# GimbalMotorController2017.net
KiCad netlist of a schematic drawn in EAGLE
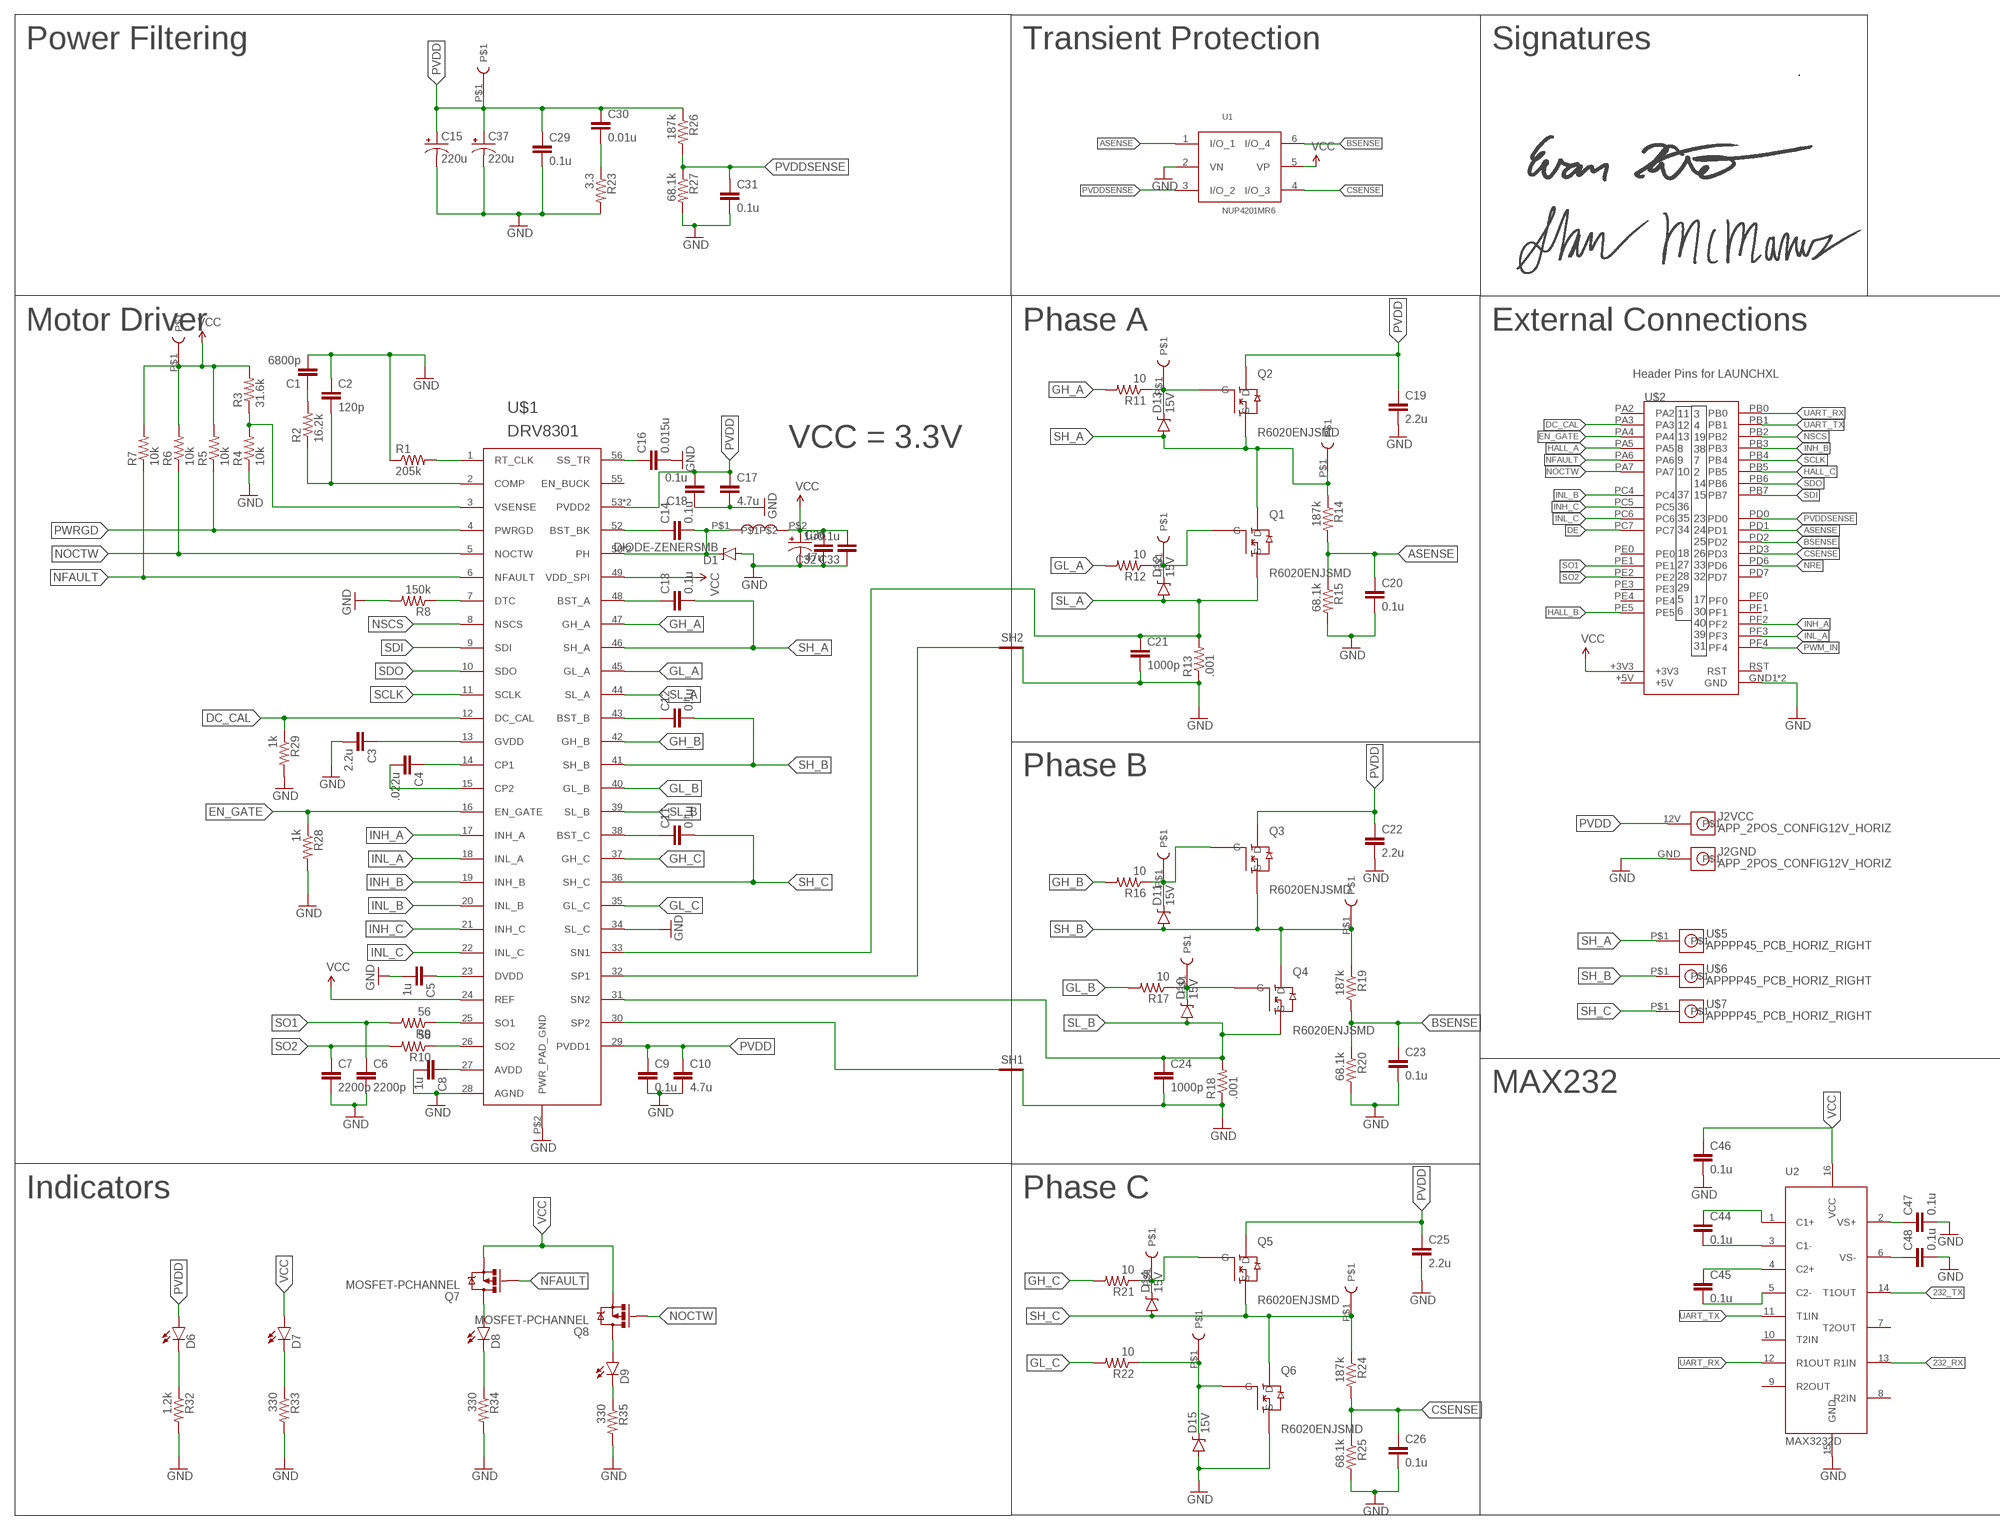
[diagram p0: schematic, sheet 1, part 1 of 2]
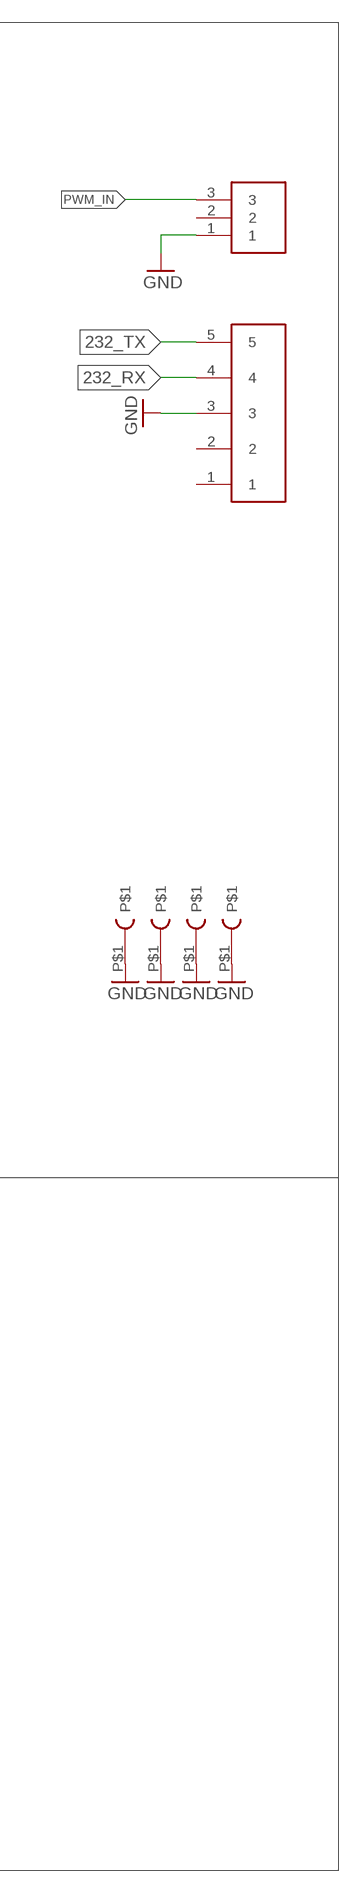
[diagram p1: schematic, sheet 1, part 2 of 2]

(export (version "E")
  (design (tool "Eeschema 10.0.6"))
  (components
    (comp (ref "C1")
      (value "6800p")
      (footprint "eagle-import:0805")
      (libsource (lib "eagle-import") (part "CAP0805"))
    )
    (comp (ref "C2")
      (value "120p")
      (footprint "eagle-import:0805")
      (libsource (lib "eagle-import") (part "CAP0805"))
    )
    (comp (ref "C3")
      (value "2.2u")
      (footprint "eagle-import:1206")
      (libsource (lib "eagle-import") (part "CAP1206"))
    )
    (comp (ref "C4")
      (value ".022u")
      (footprint "eagle-import:0805")
      (libsource (lib "eagle-import") (part "CAP0805"))
    )
    (comp (ref "C5")
      (value "1u")
      (footprint "eagle-import:0805")
      (libsource (lib "eagle-import") (part "CAP0805"))
    )
    (comp (ref "C6")
      (value "2200p")
      (footprint "eagle-import:0805")
      (libsource (lib "eagle-import") (part "CAP0805"))
    )
    (comp (ref "C7")
      (value "2200p")
      (footprint "eagle-import:0805")
      (libsource (lib "eagle-import") (part "CAP0805"))
    )
    (comp (ref "C8")
      (value "1u")
      (footprint "eagle-import:0805")
      (libsource (lib "eagle-import") (part "CAP0805"))
    )
    (comp (ref "C9")
      (value "0.1u")
      (footprint "eagle-import:0805")
      (libsource (lib "eagle-import") (part "CAP0805"))
    )
    (comp (ref "C10")
      (value "4.7u")
      (footprint "eagle-import:1206")
      (libsource (lib "eagle-import") (part "CAP1206"))
    )
    (comp (ref "C11")
      (value "0.1u")
      (footprint "eagle-import:0805")
      (libsource (lib "eagle-import") (part "CAP0805"))
    )
    (comp (ref "C12")
      (value "0.1u")
      (footprint "eagle-import:0805")
      (libsource (lib "eagle-import") (part "CAP0805"))
    )
    (comp (ref "C13")
      (value "0.1u")
      (footprint "eagle-import:0805")
      (libsource (lib "eagle-import") (part "CAP0805"))
    )
    (comp (ref "C14")
      (value "0.1u")
      (footprint "eagle-import:0805")
      (libsource (lib "eagle-import") (part "CAP0805"))
    )
    (comp (ref "C15")
      (value "220u")
      (footprint "eagle-import:CPOL-RADIAL-1000UF-25V")
      (libsource (lib "eagle-import") (part "CAP_POLPTH4"))
    )
    (comp (ref "C16")
      (value "0.015u")
      (footprint "eagle-import:0805")
      (libsource (lib "eagle-import") (part "CAP0805"))
    )
    (comp (ref "C17")
      (value "4.7u")
      (footprint "eagle-import:1206")
      (libsource (lib "eagle-import") (part "CAP1206"))
    )
    (comp (ref "C18")
      (value "0.1u")
      (footprint "eagle-import:0805")
      (libsource (lib "eagle-import") (part "CAP0805"))
    )
    (comp (ref "C19")
      (value "2.2u")
      (footprint "eagle-import:1206")
      (libsource (lib "eagle-import") (part "CAP1206"))
    )
    (comp (ref "C20")
      (value "0.1u")
      (footprint "eagle-import:0805")
      (libsource (lib "eagle-import") (part "CAP0805"))
    )
    (comp (ref "C21")
      (value "1000p")
      (footprint "eagle-import:0805")
      (libsource (lib "eagle-import") (part "CAP0805"))
    )
    (comp (ref "C22")
      (value "2.2u")
      (footprint "eagle-import:1206")
      (libsource (lib "eagle-import") (part "CAP1206"))
    )
    (comp (ref "C23")
      (value "0.1u")
      (footprint "eagle-import:0805")
      (libsource (lib "eagle-import") (part "CAP0805"))
    )
    (comp (ref "C24")
      (value "1000p")
      (footprint "eagle-import:0805")
      (libsource (lib "eagle-import") (part "CAP0805"))
    )
    (comp (ref "C25")
      (value "2.2u")
      (footprint "eagle-import:1206")
      (libsource (lib "eagle-import") (part "CAP1206"))
    )
    (comp (ref "C26")
      (value "0.1u")
      (footprint "eagle-import:0805")
      (libsource (lib "eagle-import") (part "CAP0805"))
    )
    (comp (ref "C29")
      (value "0.1u")
      (footprint "eagle-import:0805")
      (libsource (lib "eagle-import") (part "CAP0805"))
    )
    (comp (ref "C30")
      (value "0.01u")
      (footprint "eagle-import:0805")
      (libsource (lib "eagle-import") (part "CAP0805"))
    )
    (comp (ref "C31")
      (value "0.1u")
      (footprint "eagle-import:0805")
      (libsource (lib "eagle-import") (part "CAP0805"))
    )
    (comp (ref "C32")
      (value "1u")
      (footprint "eagle-import:0805")
      (libsource (lib "eagle-import") (part "CAP0805"))
    )
    (comp (ref "C33")
      (value "0.1u")
      (footprint "eagle-import:0805")
      (libsource (lib "eagle-import") (part "CAP0805"))
    )
    (comp (ref "C36")
      (value "47u")
      (footprint "eagle-import:CPOL-RADIAL-100UF-25V")
      (libsource (lib "eagle-import") (part "CAP_POLPTH1"))
    )
    (comp (ref "C37")
      (value "220u")
      (footprint "eagle-import:CPOL-RADIAL-1000UF-25V")
      (libsource (lib "eagle-import") (part "CAP_POLPTH4"))
    )
    (comp (ref "C44")
      (value "0.1u")
      (footprint "eagle-import:0805")
      (libsource (lib "eagle-import") (part "CAP0805"))
    )
    (comp (ref "C45")
      (value "0.1u")
      (footprint "eagle-import:0805")
      (libsource (lib "eagle-import") (part "CAP0805"))
    )
    (comp (ref "C46")
      (value "0.1u")
      (footprint "eagle-import:0805")
      (libsource (lib "eagle-import") (part "CAP0805"))
    )
    (comp (ref "C47")
      (value "0.1u")
      (footprint "eagle-import:0805")
      (libsource (lib "eagle-import") (part "CAP0805"))
    )
    (comp (ref "C48")
      (value "0.1u")
      (footprint "eagle-import:0805")
      (libsource (lib "eagle-import") (part "CAP0805"))
    )
    (comp (ref "D1")
      (value "DIODE-ZENERSMB")
      (footprint "eagle-import:SMB-DIODE")
      (libsource (lib "eagle-import") (part "DIODE-ZENERSMB"))
    )
    (comp (ref "D6")
      (value "LED1206")
      (footprint "eagle-import:LED-1206")
      (libsource (lib "eagle-import") (part "LED1206"))
    )
    (comp (ref "D7")
      (value "LED1206")
      (footprint "eagle-import:LED-1206")
      (libsource (lib "eagle-import") (part "LED1206"))
    )
    (comp (ref "D8")
      (value "LED1206")
      (footprint "eagle-import:LED-1206")
      (libsource (lib "eagle-import") (part "LED1206"))
    )
    (comp (ref "D9")
      (value "LED1206")
      (footprint "eagle-import:LED-1206")
      (libsource (lib "eagle-import") (part "LED1206"))
    )
    (comp (ref "D10")
      (value "15V")
      (footprint "eagle-import:SOD-323")
      (libsource (lib "eagle-import") (part "DIODE-ZENER3.3V"))
    )
    (comp (ref "D11")
      (value "15V")
      (footprint "eagle-import:SOD-323")
      (libsource (lib "eagle-import") (part "DIODE-ZENER3.3V"))
    )
    (comp (ref "D12")
      (value "15V")
      (footprint "eagle-import:SOD-323")
      (libsource (lib "eagle-import") (part "DIODE-ZENER3.3V"))
    )
    (comp (ref "D13")
      (value "15V")
      (footprint "eagle-import:SOD-323")
      (libsource (lib "eagle-import") (part "DIODE-ZENER3.3V"))
    )
    (comp (ref "D14")
      (value "15V")
      (footprint "eagle-import:SOD-323")
      (libsource (lib "eagle-import") (part "DIODE-ZENER3.3V"))
    )
    (comp (ref "D15")
      (value "15V")
      (footprint "eagle-import:SOD-323")
      (libsource (lib "eagle-import") (part "DIODE-ZENER3.3V"))
    )
    (comp (ref "J1")
      (value "SL03THROUGH_HOLE")
      (footprint "eagle-import:MOLEX_SL_03_TH")
      (fields (field (name "PARTNO") "0705550002"))
      (libsource (lib "eagle-import") (part "SL03THROUGH_HOLE"))
    )
    (comp (ref "J2")
      (value "APP_2POS_CONFIG12V_HORIZ")
      (footprint "eagle-import:APP45_12V_HORIZ_CONFIG")
      (libsource (lib "eagle-import") (part "APP_2POS_CONFIG12V_HORIZ"))
    )
    (comp (ref "Q1")
      (value "R6020ENJSMD")
      (footprint "eagle-import:D2PACK")
      (libsource (lib "eagle-import") (part "R6020ENJSMD"))
    )
    (comp (ref "Q2")
      (value "R6020ENJSMD")
      (footprint "eagle-import:D2PACK")
      (libsource (lib "eagle-import") (part "R6020ENJSMD"))
    )
    (comp (ref "Q3")
      (value "R6020ENJSMD")
      (footprint "eagle-import:D2PACK")
      (libsource (lib "eagle-import") (part "R6020ENJSMD"))
    )
    (comp (ref "Q4")
      (value "R6020ENJSMD")
      (footprint "eagle-import:D2PACK")
      (libsource (lib "eagle-import") (part "R6020ENJSMD"))
    )
    (comp (ref "Q5")
      (value "R6020ENJSMD")
      (footprint "eagle-import:D2PACK")
      (libsource (lib "eagle-import") (part "R6020ENJSMD"))
    )
    (comp (ref "Q6")
      (value "R6020ENJSMD")
      (footprint "eagle-import:D2PACK")
      (libsource (lib "eagle-import") (part "R6020ENJSMD"))
    )
    (comp (ref "Q7")
      (value "MOSFET-PCHANNEL")
      (footprint "eagle-import:SOT23-3")
      (libsource (lib "eagle-import") (part "MOSFET-PCHANNEL"))
    )
    (comp (ref "Q8")
      (value "MOSFET-PCHANNEL")
      (footprint "eagle-import:SOT23-3")
      (libsource (lib "eagle-import") (part "MOSFET-PCHANNEL"))
    )
    (comp (ref "R1")
      (value "205k")
      (footprint "eagle-import:0805")
      (libsource (lib "eagle-import") (part "RESISTOR0805-RES"))
    )
    (comp (ref "R2")
      (value "16.2k")
      (footprint "eagle-import:0805")
      (libsource (lib "eagle-import") (part "RESISTOR0805-RES"))
    )
    (comp (ref "R3")
      (value "31.6k")
      (footprint "eagle-import:0805")
      (libsource (lib "eagle-import") (part "RESISTOR0805-RES"))
    )
    (comp (ref "R4")
      (value "10k")
      (footprint "eagle-import:0805")
      (libsource (lib "eagle-import") (part "RESISTOR0805-RES"))
    )
    (comp (ref "R5")
      (value "10k")
      (footprint "eagle-import:0805")
      (libsource (lib "eagle-import") (part "RESISTOR0805-RES"))
    )
    (comp (ref "R6")
      (value "10k")
      (footprint "eagle-import:0805")
      (libsource (lib "eagle-import") (part "RESISTOR0805-RES"))
    )
    (comp (ref "R7")
      (value "10k")
      (footprint "eagle-import:0805")
      (libsource (lib "eagle-import") (part "RESISTOR0805-RES"))
    )
    (comp (ref "R8")
      (value "150k")
      (footprint "eagle-import:0805")
      (libsource (lib "eagle-import") (part "RESISTOR0805-RES"))
    )
    (comp (ref "R9")
      (value "56")
      (footprint "eagle-import:0805")
      (libsource (lib "eagle-import") (part "RESISTOR0805-RES"))
    )
    (comp (ref "R10")
      (value "56")
      (footprint "eagle-import:0805")
      (libsource (lib "eagle-import") (part "RESISTOR0805-RES"))
    )
    (comp (ref "R11")
      (value "10")
      (footprint "eagle-import:0805")
      (libsource (lib "eagle-import") (part "RESISTOR0805-RES"))
    )
    (comp (ref "R12")
      (value "10")
      (footprint "eagle-import:0805")
      (libsource (lib "eagle-import") (part "RESISTOR0805-RES"))
    )
    (comp (ref "R13")
      (value ".001")
      (footprint "eagle-import:1206")
      (libsource (lib "eagle-import") (part "RESISTOR1206"))
    )
    (comp (ref "R14")
      (value "187k")
      (footprint "eagle-import:0805")
      (libsource (lib "eagle-import") (part "RESISTOR0805-RES"))
    )
    (comp (ref "R15")
      (value "68.1k")
      (footprint "eagle-import:0805")
      (libsource (lib "eagle-import") (part "RESISTOR0805-RES"))
    )
    (comp (ref "R16")
      (value "10")
      (footprint "eagle-import:0805")
      (libsource (lib "eagle-import") (part "RESISTOR0805-RES"))
    )
    (comp (ref "R17")
      (value "10")
      (footprint "eagle-import:0805")
      (libsource (lib "eagle-import") (part "RESISTOR0805-RES"))
    )
    (comp (ref "R18")
      (value ".001")
      (footprint "eagle-import:1206")
      (libsource (lib "eagle-import") (part "RESISTOR1206"))
    )
    (comp (ref "R19")
      (value "187k")
      (footprint "eagle-import:0805")
      (libsource (lib "eagle-import") (part "RESISTOR0805-RES"))
    )
    (comp (ref "R20")
      (value "68.1k")
      (footprint "eagle-import:0805")
      (libsource (lib "eagle-import") (part "RESISTOR0805-RES"))
    )
    (comp (ref "R21")
      (value "10")
      (footprint "eagle-import:0805")
      (libsource (lib "eagle-import") (part "RESISTOR0805-RES"))
    )
    (comp (ref "R22")
      (value "10")
      (footprint "eagle-import:0805")
      (libsource (lib "eagle-import") (part "RESISTOR0805-RES"))
    )
    (comp (ref "R23")
      (value "3.3")
      (footprint "eagle-import:0805")
      (libsource (lib "eagle-import") (part "RESISTOR0805-RES"))
    )
    (comp (ref "R24")
      (value "187k")
      (footprint "eagle-import:0805")
      (libsource (lib "eagle-import") (part "RESISTOR0805-RES"))
    )
    (comp (ref "R25")
      (value "68.1k")
      (footprint "eagle-import:0805")
      (libsource (lib "eagle-import") (part "RESISTOR0805-RES"))
    )
    (comp (ref "R26")
      (value "187k")
      (footprint "eagle-import:0805")
      (libsource (lib "eagle-import") (part "RESISTOR0805-RES"))
    )
    (comp (ref "R27")
      (value "68.1k")
      (footprint "eagle-import:0805")
      (libsource (lib "eagle-import") (part "RESISTOR0805-RES"))
    )
    (comp (ref "R28")
      (value "1k")
      (footprint "eagle-import:0805")
      (libsource (lib "eagle-import") (part "RESISTOR0805-RES"))
    )
    (comp (ref "R29")
      (value "1k")
      (footprint "eagle-import:0805")
      (libsource (lib "eagle-import") (part "RESISTOR0805-RES"))
    )
    (comp (ref "R32")
      (value "1.2k")
      (footprint "eagle-import:0805")
      (libsource (lib "eagle-import") (part "RESISTOR0805-RES"))
    )
    (comp (ref "R33")
      (value "330")
      (footprint "eagle-import:0805")
      (libsource (lib "eagle-import") (part "RESISTOR0805-RES"))
    )
    (comp (ref "R34")
      (value "330")
      (footprint "eagle-import:0805")
      (libsource (lib "eagle-import") (part "RESISTOR0805-RES"))
    )
    (comp (ref "R35")
      (value "330")
      (footprint "eagle-import:0805")
      (libsource (lib "eagle-import") (part "RESISTOR0805-RES"))
    )
    (comp (ref "SH1")
      (value "SHORT-HT5")
      (footprint "eagle-import:SHORT_TOP-50")
      (libsource (lib "eagle-import") (part "SHORT-HT5"))
    )
    (comp (ref "SH2")
      (value "SHORT-HT5")
      (footprint "eagle-import:SHORT_TOP-50")
      (libsource (lib "eagle-import") (part "SHORT-HT5"))
    )
    (comp (ref "U$1")
      (value "DRV8301")
      (footprint "eagle-import:TFSOP-56")
      (libsource (lib "eagle-import") (part "DRV8301"))
    )
    (comp (ref "U$2")
      (value "TIVA-C")
      (footprint "eagle-import:TIVA-C")
      (libsource (lib "eagle-import") (part "TIVA-C"))
    )
    (comp (ref "U$3")
      (value "TEST_POINT_0.1INDIAM")
      (footprint "eagle-import:TEST_POINT_0.1INDIAM")
      (libsource (lib "eagle-import") (part "TEST_POINT_0.1INDIAM"))
    )
    (comp (ref "U$4")
      (value "5PIN")
      (footprint "eagle-import:5PIN")
      (libsource (lib "eagle-import") (part "5PIN"))
    )
    (comp (ref "U$5")
      (value "APPPP45_PCB_HORIZ_RIGHT")
      (footprint "eagle-import:APP45_PCB_HORIZ_RIGHT")
      (libsource (lib "eagle-import") (part "APPPP45_PCB_HORIZ_RIGHT"))
    )
    (comp (ref "U$6")
      (value "APPPP45_PCB_HORIZ_RIGHT")
      (footprint "eagle-import:APP45_PCB_HORIZ_RIGHT")
      (libsource (lib "eagle-import") (part "APPPP45_PCB_HORIZ_RIGHT"))
    )
    (comp (ref "U$7")
      (value "APPPP45_PCB_HORIZ_RIGHT")
      (footprint "eagle-import:APP45_PCB_HORIZ_RIGHT")
      (libsource (lib "eagle-import") (part "APPPP45_PCB_HORIZ_RIGHT"))
    )
    (comp (ref "U$8")
      (value "SHAUN_MCMANUS_SIGNATURE")
      (footprint "eagle-import:SHAUN_MCMANUS_SIGNATURE")
      (libsource (lib "eagle-import") (part "SHAUN_MCMANUS_SIGNATURE"))
    )
    (comp (ref "U$10")
      (value "TEST_POINT_0.1INDIAM")
      (footprint "eagle-import:TEST_POINT_0.1INDIAM")
      (libsource (lib "eagle-import") (part "TEST_POINT_0.1INDIAM"))
    )
    (comp (ref "U$11")
      (value "EVAN_HITE_SIGNATURE")
      (footprint "eagle-import:EVAN_HITE_SIGNATURE")
      (libsource (lib "eagle-import") (part "EVAN_HITE_SIGNATURE"))
    )
    (comp (ref "U$12")
      (value "TEST_POINT_0.1INDIAM")
      (footprint "eagle-import:TEST_POINT_0.1INDIAM")
      (libsource (lib "eagle-import") (part "TEST_POINT_0.1INDIAM"))
    )
    (comp (ref "U$14")
      (value "33u")
      (footprint "eagle-import:INDUCTOR_DR74")
      (libsource (lib "eagle-import") (part "INDUCTOR_DR74"))
    )
    (comp (ref "U$15")
      (value "TEST_POINT_0.1INDIAM")
      (footprint "eagle-import:TEST_POINT_0.1INDIAM")
      (libsource (lib "eagle-import") (part "TEST_POINT_0.1INDIAM"))
    )
    (comp (ref "U$16")
      (value "TEST_POINT_0.1INDIAM")
      (footprint "eagle-import:TEST_POINT_0.1INDIAM")
      (libsource (lib "eagle-import") (part "TEST_POINT_0.1INDIAM"))
    )
    (comp (ref "U$17")
      (value "TEST_POINT_0.1INDIAM")
      (footprint "eagle-import:TEST_POINT_0.1INDIAM")
      (libsource (lib "eagle-import") (part "TEST_POINT_0.1INDIAM"))
    )
    (comp (ref "U$18")
      (value "TEST_POINT_0.1INDIAM")
      (footprint "eagle-import:TEST_POINT_0.1INDIAM")
      (libsource (lib "eagle-import") (part "TEST_POINT_0.1INDIAM"))
    )
    (comp (ref "U$19")
      (value "TEST_POINT_0.1INDIAM")
      (footprint "eagle-import:TEST_POINT_0.1INDIAM")
      (libsource (lib "eagle-import") (part "TEST_POINT_0.1INDIAM"))
    )
    (comp (ref "U$20")
      (value "TEST_POINT_0.1INDIAM")
      (footprint "eagle-import:TEST_POINT_0.1INDIAM")
      (libsource (lib "eagle-import") (part "TEST_POINT_0.1INDIAM"))
    )
    (comp (ref "U$24")
      (value "TEST_POINT_0.1INDIAM")
      (footprint "eagle-import:TEST_POINT_0.1INDIAM")
      (libsource (lib "eagle-import") (part "TEST_POINT_0.1INDIAM"))
    )
    (comp (ref "U$25")
      (value "TEST_POINT_0.1INDIAM")
      (footprint "eagle-import:TEST_POINT_0.1INDIAM")
      (libsource (lib "eagle-import") (part "TEST_POINT_0.1INDIAM"))
    )
    (comp (ref "U$26")
      (value "TEST_POINT_0.1INDIAM")
      (footprint "eagle-import:TEST_POINT_0.1INDIAM")
      (libsource (lib "eagle-import") (part "TEST_POINT_0.1INDIAM"))
    )
    (comp (ref "U$27")
      (value "TEST_POINT_0.1INDIAM")
      (footprint "eagle-import:TEST_POINT_0.1INDIAM")
      (libsource (lib "eagle-import") (part "TEST_POINT_0.1INDIAM"))
    )
    (comp (ref "U$28")
      (value "TEST_POINT_0.1INDIAM")
      (footprint "eagle-import:TEST_POINT_0.1INDIAM")
      (libsource (lib "eagle-import") (part "TEST_POINT_0.1INDIAM"))
    )
    (comp (ref "U$29")
      (value "TEST_POINT_0.1INDIAM")
      (footprint "eagle-import:TEST_POINT_0.1INDIAM")
      (libsource (lib "eagle-import") (part "TEST_POINT_0.1INDIAM"))
    )
    (comp (ref "U1")
      (value "NUP4201MR6")
      (footprint "eagle-import:TSOP-6")
      (libsource (lib "eagle-import") (part "NUP4201MR6"))
    )
    (comp (ref "U2")
      (value "MAX3232D")
      (footprint "eagle-import:SOIC16")
      (libsource (lib "eagle-import") (part "MAX232D3"))
    )
  )
  (nets
    (net (code "1") (name "/+5V") (class "Default")
      (node (ref "U$2") (pin "+5V") (pinfunction "+5V_+5V") (pintype "power_in"))
    )
    (net (code "2") (name "/RST") (class "Default")
      (node (ref "U$2") (pin "RST") (pinfunction "RST_RST") (pintype "power_in"))
    )
    (net (code "3") (name "232_RX") (class "Default")
      (node (ref "U$4") (pin "4") (pinfunction "4_4") (pintype "bidirectional"))
      (node (ref "U2") (pin "13") (pinfunction "R1IN_13") (pintype "bidirectional"))
    )
    (net (code "4") (name "232_TX") (class "Default")
      (node (ref "U$4") (pin "5") (pinfunction "5_5") (pintype "bidirectional"))
      (node (ref "U2") (pin "14") (pinfunction "T1OUT_14") (pintype "bidirectional"))
    )
    (net (code "5") (name "ASENSE") (class "Default")
      (node (ref "C20") (pin "1") (pinfunction "1_1") (pintype "passive"))
      (node (ref "R14") (pin "2") (pinfunction "2_2") (pintype "passive"))
      (node (ref "R15") (pin "1") (pinfunction "1_1") (pintype "passive"))
      (node (ref "U$2") (pin "PD1") (pinfunction "PD1_PD1") (pintype "bidirectional"))
      (node (ref "U1") (pin "1") (pinfunction "I/O_1_1") (pintype "bidirectional"))
    )
    (net (code "6") (name "BSENSE") (class "Default")
      (node (ref "C23") (pin "1") (pinfunction "1_1") (pintype "passive"))
      (node (ref "R19") (pin "2") (pinfunction "2_2") (pintype "passive"))
      (node (ref "R20") (pin "1") (pinfunction "1_1") (pintype "passive"))
      (node (ref "U$2") (pin "PD2") (pinfunction "PD2_PD2") (pintype "bidirectional"))
      (node (ref "U1") (pin "6") (pinfunction "I/O_4_6") (pintype "bidirectional"))
    )
    (net (code "7") (name "CSENSE") (class "Default")
      (node (ref "C26") (pin "1") (pinfunction "1_1") (pintype "passive"))
      (node (ref "R24") (pin "2") (pinfunction "2_2") (pintype "passive"))
      (node (ref "R25") (pin "1") (pinfunction "1_1") (pintype "passive"))
      (node (ref "U$2") (pin "PD3") (pinfunction "PD3_PD3") (pintype "bidirectional"))
      (node (ref "U1") (pin "4") (pinfunction "I/O_3_4") (pintype "bidirectional"))
    )
    (net (code "8") (name "DC_CAL") (class "Default")
      (node (ref "R29") (pin "1") (pinfunction "1_1") (pintype "passive"))
      (node (ref "U$1") (pin "12") (pinfunction "DC_CAL_12") (pintype "bidirectional"))
      (node (ref "U$2") (pin "PA3") (pinfunction "PA3_PA3") (pintype "bidirectional"))
    )
    (net (code "9") (name "DE") (class "Default")
      (node (ref "U$2") (pin "PC7") (pinfunction "PC7_PC7") (pintype "bidirectional"))
    )
    (net (code "10") (name "EN_GATE") (class "Default")
      (node (ref "R28") (pin "1") (pinfunction "1_1") (pintype "passive"))
      (node (ref "U$1") (pin "16") (pinfunction "EN_GATE_16") (pintype "bidirectional"))
      (node (ref "U$2") (pin "PA4") (pinfunction "PA4_PA4") (pintype "bidirectional"))
    )
    (net (code "11") (name "GH_A") (class "Default")
      (node (ref "R11") (pin "2") (pinfunction "2_2") (pintype "passive"))
      (node (ref "U$1") (pin "47") (pinfunction "GH_A_47") (pintype "bidirectional"))
    )
    (net (code "12") (name "GH_B") (class "Default")
      (node (ref "R16") (pin "2") (pinfunction "2_2") (pintype "passive"))
      (node (ref "U$1") (pin "42") (pinfunction "GH_B_42") (pintype "bidirectional"))
    )
    (net (code "13") (name "GH_C") (class "Default")
      (node (ref "R21") (pin "2") (pinfunction "2_2") (pintype "passive"))
      (node (ref "U$1") (pin "37") (pinfunction "GH_C_37") (pintype "bidirectional"))
    )
    (net (code "14") (name "GL_A") (class "Default")
      (node (ref "R12") (pin "2") (pinfunction "2_2") (pintype "passive"))
      (node (ref "U$1") (pin "45") (pinfunction "GL_A_45") (pintype "bidirectional"))
    )
    (net (code "15") (name "GL_B") (class "Default")
      (node (ref "R17") (pin "2") (pinfunction "2_2") (pintype "passive"))
      (node (ref "U$1") (pin "40") (pinfunction "GL_B_40") (pintype "bidirectional"))
    )
    (net (code "16") (name "GL_C") (class "Default")
      (node (ref "R22") (pin "2") (pinfunction "2_2") (pintype "passive"))
      (node (ref "U$1") (pin "35") (pinfunction "GL_C_35") (pintype "bidirectional"))
    )
    (net (code "17") (name "GND") (class "Default")
      (node (ref "C1") (pin "2") (pinfunction "2_2") (pintype "passive"))
      (node (ref "C10") (pin "2") (pinfunction "2_2") (pintype "passive"))
      (node (ref "C15") (pin "2") (pinfunction "-_2") (pintype "passive"))
      (node (ref "C16") (pin "2") (pinfunction "2_2") (pintype "passive"))
      (node (ref "C17") (pin "2") (pinfunction "2_2") (pintype "passive"))
      (node (ref "C18") (pin "1") (pinfunction "1_1") (pintype "passive"))
      (node (ref "C19") (pin "2") (pinfunction "2_2") (pintype "passive"))
      (node (ref "C2") (pin "1") (pinfunction "1_1") (pintype "passive"))
      (node (ref "C20") (pin "2") (pinfunction "2_2") (pintype "passive"))
      (node (ref "C21") (pin "2") (pinfunction "2_2") (pintype "passive"))
      (node (ref "C22") (pin "2") (pinfunction "2_2") (pintype "passive"))
      (node (ref "C23") (pin "2") (pinfunction "2_2") (pintype "passive"))
      (node (ref "C24") (pin "2") (pinfunction "2_2") (pintype "passive"))
      (node (ref "C25") (pin "2") (pinfunction "2_2") (pintype "passive"))
      (node (ref "C26") (pin "2") (pinfunction "2_2") (pintype "passive"))
      (node (ref "C29") (pin "2") (pinfunction "2_2") (pintype "passive"))
      (node (ref "C3") (pin "2") (pinfunction "2_2") (pintype "passive"))
      (node (ref "C31") (pin "2") (pinfunction "2_2") (pintype "passive"))
      (node (ref "C32") (pin "1") (pinfunction "1_1") (pintype "passive"))
      (node (ref "C33") (pin "1") (pinfunction "1_1") (pintype "passive"))
      (node (ref "C36") (pin "2") (pinfunction "-_2") (pintype "passive"))
      (node (ref "C37") (pin "2") (pinfunction "-_2") (pintype "passive"))
      (node (ref "C46") (pin "2") (pinfunction "2_2") (pintype "passive"))
      (node (ref "C47") (pin "2") (pinfunction "2_2") (pintype "passive"))
      (node (ref "C48") (pin "2") (pinfunction "2_2") (pintype "passive"))
      (node (ref "C5") (pin "2") (pinfunction "2_2") (pintype "passive"))
      (node (ref "C6") (pin "2") (pinfunction "2_2") (pintype "passive"))
      (node (ref "C7") (pin "2") (pinfunction "2_2") (pintype "passive"))
      (node (ref "C8") (pin "2") (pinfunction "2_2") (pintype "passive"))
      (node (ref "C9") (pin "2") (pinfunction "2_2") (pintype "passive"))
      (node (ref "D1") (pin "A") (pinfunction "A_A") (pintype "passive"))
      (node (ref "D15") (pin "A") (pinfunction "A_A") (pintype "passive"))
      (node (ref "J1") (pin "1") (pinfunction "1_1") (pintype "bidirectional"))
      (node (ref "J2") (pin "GND") (pinfunction "P$1_GND") (pintype "bidirectional"))
      (node (ref "Q6") (pin "2") (pinfunction "S_2") (pintype "bidirectional"))
      (node (ref "R1") (pin "1") (pinfunction "1_1") (pintype "passive"))
      (node (ref "R13") (pin "1") (pinfunction "1_1") (pintype "passive"))
      (node (ref "R15") (pin "2") (pinfunction "2_2") (pintype "passive"))
      (node (ref "R18") (pin "1") (pinfunction "1_1") (pintype "passive"))
      (node (ref "R20") (pin "2") (pinfunction "2_2") (pintype "passive"))
      (node (ref "R23") (pin "2") (pinfunction "2_2") (pintype "passive"))
      (node (ref "R25") (pin "2") (pinfunction "2_2") (pintype "passive"))
      (node (ref "R27") (pin "2") (pinfunction "2_2") (pintype "passive"))
      (node (ref "R28") (pin "2") (pinfunction "2_2") (pintype "passive"))
      (node (ref "R29") (pin "2") (pinfunction "2_2") (pintype "passive"))
      (node (ref "R32") (pin "2") (pinfunction "2_2") (pintype "passive"))
      (node (ref "R33") (pin "2") (pinfunction "2_2") (pintype "passive"))
      (node (ref "R34") (pin "2") (pinfunction "2_2") (pintype "passive"))
      (node (ref "R35") (pin "2") (pinfunction "2_2") (pintype "passive"))
      (node (ref "R4") (pin "1") (pinfunction "1_1") (pintype "passive"))
      (node (ref "R8") (pin "2") (pinfunction "2_2") (pintype "passive"))
      (node (ref "SH1") (pin "2") (pinfunction "P$2_2") (pintype "bidirectional"))
      (node (ref "SH2") (pin "2") (pinfunction "P$2_2") (pintype "bidirectional"))
      (node (ref "U$1") (pin "28") (pinfunction "AGND_28") (pintype "bidirectional"))
      (node (ref "U$1") (pin "34") (pinfunction "SL_C_34") (pintype "bidirectional"))
      (node (ref "U$1") (pin "P$2") (pinfunction "PWR_PAD_GND_P$2") (pintype "bidirectional"))
      (node (ref "U$2") (pin "GND1") (pinfunction "GND_GND1") (pintype "power_in"))
      (node (ref "U$2") (pin "GND2") (pinfunction "GND_GND2") (pintype "power_in"))
      (node (ref "U$26") (pin "P$1") (pinfunction "P$1_P$1") (pintype "bidirectional"))
      (node (ref "U$27") (pin "P$1") (pinfunction "P$1_P$1") (pintype "bidirectional"))
      (node (ref "U$28") (pin "P$1") (pinfunction "P$1_P$1") (pintype "bidirectional"))
      (node (ref "U$29") (pin "P$1") (pinfunction "P$1_P$1") (pintype "bidirectional"))
      (node (ref "U$4") (pin "3") (pinfunction "3_3") (pintype "bidirectional"))
      (node (ref "U1") (pin "2") (pinfunction "VN_2") (pintype "bidirectional"))
      (node (ref "U2") (pin "15") (pinfunction "GND_15") (pintype "bidirectional"))
    )
    (net (code "18") (name "HALL_A") (class "Default")
      (node (ref "U$2") (pin "PA5") (pinfunction "PA5_PA5") (pintype "bidirectional"))
    )
    (net (code "19") (name "HALL_B") (class "Default")
      (node (ref "U$2") (pin "PE5") (pinfunction "PE5_PE5") (pintype "bidirectional"))
    )
    (net (code "20") (name "HALL_C") (class "Default")
      (node (ref "U$2") (pin "PB5") (pinfunction "PB5_PB5") (pintype "bidirectional"))
    )
    (net (code "21") (name "INH_A") (class "Default")
      (node (ref "U$1") (pin "17") (pinfunction "INH_A_17") (pintype "bidirectional"))
      (node (ref "U$2") (pin "PF2") (pinfunction "PF2_PF2") (pintype "bidirectional"))
    )
    (net (code "22") (name "INH_B") (class "Default")
      (node (ref "U$1") (pin "19") (pinfunction "INH_B_19") (pintype "bidirectional"))
      (node (ref "U$2") (pin "PB3") (pinfunction "PB3_PB3") (pintype "bidirectional"))
    )
    (net (code "23") (name "INH_C") (class "Default")
      (node (ref "U$1") (pin "21") (pinfunction "INH_C_21") (pintype "bidirectional"))
      (node (ref "U$2") (pin "PC5") (pinfunction "PC5_PC5") (pintype "bidirectional"))
    )
    (net (code "24") (name "INL_A") (class "Default")
      (node (ref "U$1") (pin "18") (pinfunction "INL_A_18") (pintype "bidirectional"))
      (node (ref "U$2") (pin "PF3") (pinfunction "PF3_PF3") (pintype "bidirectional"))
    )
    (net (code "25") (name "INL_B") (class "Default")
      (node (ref "U$1") (pin "20") (pinfunction "INL_B_20") (pintype "bidirectional"))
      (node (ref "U$2") (pin "PC4") (pinfunction "PC4_PC4") (pintype "bidirectional"))
    )
    (net (code "26") (name "INL_C") (class "Default")
      (node (ref "U$1") (pin "22") (pinfunction "INL_C_22") (pintype "bidirectional"))
      (node (ref "U$2") (pin "PC6") (pinfunction "PC6_PC6") (pintype "bidirectional"))
    )
    (net (code "27") (name "NFAULT") (class "Default")
      (node (ref "Q7") (pin "1") (pinfunction "G_1") (pintype "passive"))
      (node (ref "R7") (pin "1") (pinfunction "1_1") (pintype "passive"))
      (node (ref "U$1") (pin "6") (pinfunction "NFAULT_6") (pintype "bidirectional"))
      (node (ref "U$2") (pin "PA6") (pinfunction "PA6_PA6") (pintype "bidirectional"))
    )
    (net (code "28") (name "NOCTW") (class "Default")
      (node (ref "Q8") (pin "1") (pinfunction "G_1") (pintype "passive"))
      (node (ref "R6") (pin "1") (pinfunction "1_1") (pintype "passive"))
      (node (ref "U$1") (pin "5") (pinfunction "NOCTW_5") (pintype "bidirectional"))
      (node (ref "U$2") (pin "PA7") (pinfunction "PA7_PA7") (pintype "bidirectional"))
    )
    (net (code "29") (name "NRE") (class "Default")
      (node (ref "U$2") (pin "PD6") (pinfunction "PD6_PD6") (pintype "bidirectional"))
    )
    (net (code "30") (name "NSCS") (class "Default")
      (node (ref "U$1") (pin "8") (pinfunction "NSCS_8") (pintype "bidirectional"))
      (node (ref "U$2") (pin "PB2") (pinfunction "PB2_PB2") (pintype "bidirectional"))
    )
    (net (code "31") (name "Net-(C1-Pad1)") (class "Default")
      (node (ref "C1") (pin "1") (pinfunction "1_1") (pintype "passive"))
      (node (ref "R2") (pin "2") (pinfunction "2_2") (pintype "passive"))
    )
    (net (code "32") (name "Net-(C14-Pad2)") (class "Default")
      (node (ref "C14") (pin "2") (pinfunction "2_2") (pintype "passive"))
      (node (ref "D1") (pin "C") (pinfunction "C_C") (pintype "passive"))
      (node (ref "U$1") (pin "50") (pinfunction "PH_50") (pintype "bidirectional"))
      (node (ref "U$1") (pin "51") (pinfunction "PH_51") (pintype "bidirectional"))
      (node (ref "U$14") (pin "P$1") (pinfunction "P$1_P$1") (pintype "bidirectional"))
    )
    (net (code "33") (name "Net-(C30-Pad2)") (class "Default")
      (node (ref "C30") (pin "2") (pinfunction "2_2") (pintype "passive"))
      (node (ref "R23") (pin "1") (pinfunction "1_1") (pintype "passive"))
    )
    (net (code "34") (name "Net-(D6-PadC)") (class "Default")
      (node (ref "D6") (pin "C") (pinfunction "C_C") (pintype "passive"))
      (node (ref "R32") (pin "1") (pinfunction "1_1") (pintype "passive"))
    )
    (net (code "35") (name "Net-(D7-PadC)") (class "Default")
      (node (ref "D7") (pin "C") (pinfunction "C_C") (pintype "passive"))
      (node (ref "R33") (pin "1") (pinfunction "1_1") (pintype "passive"))
    )
    (net (code "36") (name "Net-(D8-PadC)") (class "Default")
      (node (ref "D8") (pin "C") (pinfunction "C_C") (pintype "passive"))
      (node (ref "R34") (pin "1") (pinfunction "1_1") (pintype "passive"))
    )
    (net (code "37") (name "Net-(D9-PadC)") (class "Default")
      (node (ref "D9") (pin "C") (pinfunction "C_C") (pintype "passive"))
      (node (ref "R35") (pin "1") (pinfunction "1_1") (pintype "passive"))
    )
    (net (code "38") (name "Net-(Q1-G)") (class "Default")
      (node (ref "D12") (pin "C") (pinfunction "C_C") (pintype "passive"))
      (node (ref "Q1") (pin "1") (pinfunction "G_1") (pintype "bidirectional"))
      (node (ref "R12") (pin "1") (pinfunction "1_1") (pintype "passive"))
      (node (ref "U$15") (pin "P$1") (pinfunction "P$1_P$1") (pintype "bidirectional"))
    )
    (net (code "39") (name "Net-(Q2-G)") (class "Default")
      (node (ref "D13") (pin "C") (pinfunction "C_C") (pintype "passive"))
      (node (ref "Q2") (pin "1") (pinfunction "G_1") (pintype "bidirectional"))
      (node (ref "R11") (pin "1") (pinfunction "1_1") (pintype "passive"))
      (node (ref "U$12") (pin "P$1") (pinfunction "P$1_P$1") (pintype "bidirectional"))
    )
    (net (code "40") (name "Net-(Q3-G)") (class "Default")
      (node (ref "D11") (pin "C") (pinfunction "C_C") (pintype "passive"))
      (node (ref "Q3") (pin "1") (pinfunction "G_1") (pintype "bidirectional"))
      (node (ref "R16") (pin "1") (pinfunction "1_1") (pintype "passive"))
      (node (ref "U$16") (pin "P$1") (pinfunction "P$1_P$1") (pintype "bidirectional"))
    )
    (net (code "41") (name "Net-(Q4-G)") (class "Default")
      (node (ref "D10") (pin "C") (pinfunction "C_C") (pintype "passive"))
      (node (ref "Q4") (pin "1") (pinfunction "G_1") (pintype "bidirectional"))
      (node (ref "R17") (pin "1") (pinfunction "1_1") (pintype "passive"))
      (node (ref "U$17") (pin "P$1") (pinfunction "P$1_P$1") (pintype "bidirectional"))
    )
    (net (code "42") (name "Net-(Q5-G)") (class "Default")
      (node (ref "D14") (pin "C") (pinfunction "C_C") (pintype "passive"))
      (node (ref "Q5") (pin "1") (pinfunction "G_1") (pintype "bidirectional"))
      (node (ref "R21") (pin "1") (pinfunction "1_1") (pintype "passive"))
      (node (ref "U$18") (pin "P$1") (pinfunction "P$1_P$1") (pintype "bidirectional"))
    )
    (net (code "43") (name "Net-(Q6-G)") (class "Default")
      (node (ref "D15") (pin "C") (pinfunction "C_C") (pintype "passive"))
      (node (ref "Q6") (pin "1") (pinfunction "G_1") (pintype "bidirectional"))
      (node (ref "R22") (pin "1") (pinfunction "1_1") (pintype "passive"))
      (node (ref "U$19") (pin "P$1") (pinfunction "P$1_P$1") (pintype "bidirectional"))
    )
    (net (code "44") (name "Net-(Q7-D)") (class "Default")
      (node (ref "D8") (pin "A") (pinfunction "A_A") (pintype "passive"))
      (node (ref "Q7") (pin "3") (pinfunction "D_3") (pintype "passive"))
    )
    (net (code "45") (name "Net-(Q8-D)") (class "Default")
      (node (ref "D9") (pin "A") (pinfunction "A_A") (pintype "passive"))
      (node (ref "Q8") (pin "3") (pinfunction "D_3") (pintype "passive"))
    )
    (net (code "46") (name "Net-(SH1-P$1)") (class "Default")
      (node (ref "SH1") (pin "1") (pinfunction "P$1_1") (pintype "bidirectional"))
      (node (ref "U$1") (pin "30") (pinfunction "SP2_30") (pintype "bidirectional"))
    )
    (net (code "47") (name "Net-(SH2-P$1)") (class "Default")
      (node (ref "SH2") (pin "1") (pinfunction "P$1_1") (pintype "bidirectional"))
      (node (ref "U$1") (pin "32") (pinfunction "SP1_32") (pintype "bidirectional"))
    )
    (net (code "48") (name "Net-(U$1-AVDD)") (class "Default")
      (node (ref "C8") (pin "1") (pinfunction "1_1") (pintype "passive"))
      (node (ref "U$1") (pin "27") (pinfunction "AVDD_27") (pintype "bidirectional"))
    )
    (net (code "49") (name "Net-(U$1-BST_A)") (class "Default")
      (node (ref "C13") (pin "1") (pinfunction "1_1") (pintype "passive"))
      (node (ref "U$1") (pin "48") (pinfunction "BST_A_48") (pintype "bidirectional"))
    )
    (net (code "50") (name "Net-(U$1-BST_B)") (class "Default")
      (node (ref "C12") (pin "1") (pinfunction "1_1") (pintype "passive"))
      (node (ref "U$1") (pin "43") (pinfunction "BST_B_43") (pintype "bidirectional"))
    )
    (net (code "51") (name "Net-(U$1-BST_BK)") (class "Default")
      (node (ref "C14") (pin "1") (pinfunction "1_1") (pintype "passive"))
      (node (ref "U$1") (pin "52") (pinfunction "BST_BK_52") (pintype "bidirectional"))
    )
    (net (code "52") (name "Net-(U$1-BST_C)") (class "Default")
      (node (ref "C11") (pin "1") (pinfunction "1_1") (pintype "passive"))
      (node (ref "U$1") (pin "38") (pinfunction "BST_C_38") (pintype "bidirectional"))
    )
    (net (code "53") (name "Net-(U$1-COMP)") (class "Default")
      (node (ref "C2") (pin "2") (pinfunction "2_2") (pintype "passive"))
      (node (ref "R2") (pin "1") (pinfunction "1_1") (pintype "passive"))
      (node (ref "U$1") (pin "2") (pinfunction "COMP_2") (pintype "bidirectional"))
    )
    (net (code "54") (name "Net-(U$1-CP1)") (class "Default")
      (node (ref "C4") (pin "1") (pinfunction "1_1") (pintype "passive"))
      (node (ref "U$1") (pin "14") (pinfunction "CP1_14") (pintype "bidirectional"))
    )
    (net (code "55") (name "Net-(U$1-CP2)") (class "Default")
      (node (ref "C4") (pin "2") (pinfunction "2_2") (pintype "passive"))
      (node (ref "U$1") (pin "15") (pinfunction "CP2_15") (pintype "bidirectional"))
    )
    (net (code "56") (name "Net-(U$1-DTC)") (class "Default")
      (node (ref "R8") (pin "1") (pinfunction "1_1") (pintype "passive"))
      (node (ref "U$1") (pin "7") (pinfunction "DTC_7") (pintype "bidirectional"))
    )
    (net (code "57") (name "Net-(U$1-DVDD)") (class "Default")
      (node (ref "C5") (pin "1") (pinfunction "1_1") (pintype "passive"))
      (node (ref "U$1") (pin "23") (pinfunction "DVDD_23") (pintype "bidirectional"))
    )
    (net (code "58") (name "Net-(U$1-GVDD)") (class "Default")
      (node (ref "C3") (pin "1") (pinfunction "1_1") (pintype "passive"))
      (node (ref "U$1") (pin "13") (pinfunction "GVDD_13") (pintype "bidirectional"))
    )
    (net (code "59") (name "Net-(U$1-RT_CLK)") (class "Default")
      (node (ref "R1") (pin "2") (pinfunction "2_2") (pintype "passive"))
      (node (ref "U$1") (pin "1") (pinfunction "RT_CLK_1") (pintype "bidirectional"))
    )
    (net (code "60") (name "Net-(U$1-SO1)") (class "Default")
      (node (ref "R9") (pin "1") (pinfunction "1_1") (pintype "passive"))
      (node (ref "U$1") (pin "25") (pinfunction "SO1_25") (pintype "bidirectional"))
    )
    (net (code "61") (name "Net-(U$1-SO2)") (class "Default")
      (node (ref "R10") (pin "1") (pinfunction "1_1") (pintype "passive"))
      (node (ref "U$1") (pin "26") (pinfunction "SO2_26") (pintype "bidirectional"))
    )
    (net (code "62") (name "Net-(U$1-SS_TR)") (class "Default")
      (node (ref "C16") (pin "1") (pinfunction "1_1") (pintype "passive"))
      (node (ref "U$1") (pin "56") (pinfunction "SS_TR_56") (pintype "bidirectional"))
    )
    (net (code "63") (name "Net-(U$1-VSENSE)") (class "Default")
      (node (ref "R3") (pin "1") (pinfunction "1_1") (pintype "passive"))
      (node (ref "R4") (pin "2") (pinfunction "2_2") (pintype "passive"))
      (node (ref "U$1") (pin "3") (pinfunction "VSENSE_3") (pintype "bidirectional"))
    )
    (net (code "64") (name "Net-(U2-C1+)") (class "Default")
      (node (ref "C44") (pin "1") (pinfunction "1_1") (pintype "passive"))
      (node (ref "U2") (pin "1") (pinfunction "C1+_1") (pintype "bidirectional"))
    )
    (net (code "65") (name "Net-(U2-C1-)") (class "Default")
      (node (ref "C44") (pin "2") (pinfunction "2_2") (pintype "passive"))
      (node (ref "U2") (pin "3") (pinfunction "C1-_3") (pintype "bidirectional"))
    )
    (net (code "66") (name "Net-(U2-C2+)") (class "Default")
      (node (ref "C45") (pin "1") (pinfunction "1_1") (pintype "passive"))
      (node (ref "U2") (pin "4") (pinfunction "C2+_4") (pintype "bidirectional"))
    )
    (net (code "67") (name "Net-(U2-C2-)") (class "Default")
      (node (ref "C45") (pin "2") (pinfunction "2_2") (pintype "passive"))
      (node (ref "U2") (pin "5") (pinfunction "C2-_5") (pintype "bidirectional"))
    )
    (net (code "68") (name "Net-(U2-VS+)") (class "Default")
      (node (ref "C47") (pin "1") (pinfunction "1_1") (pintype "passive"))
      (node (ref "U2") (pin "2") (pinfunction "VS+_2") (pintype "bidirectional"))
    )
    (net (code "69") (name "Net-(U2-VS-)") (class "Default")
      (node (ref "C48") (pin "1") (pinfunction "1_1") (pintype "passive"))
      (node (ref "U2") (pin "6") (pinfunction "VS-_6") (pintype "bidirectional"))
    )
    (net (code "70") (name "PVDD") (class "Default")
      (node (ref "C10") (pin "1") (pinfunction "1_1") (pintype "passive"))
      (node (ref "C15") (pin "1") (pinfunction "+_1") (pintype "passive"))
      (node (ref "C17") (pin "1") (pinfunction "1_1") (pintype "passive"))
      (node (ref "C18") (pin "2") (pinfunction "2_2") (pintype "passive"))
      (node (ref "C19") (pin "1") (pinfunction "1_1") (pintype "passive"))
      (node (ref "C22") (pin "1") (pinfunction "1_1") (pintype "passive"))
      (node (ref "C25") (pin "1") (pinfunction "1_1") (pintype "passive"))
      (node (ref "C29") (pin "1") (pinfunction "1_1") (pintype "passive"))
      (node (ref "C30") (pin "1") (pinfunction "1_1") (pintype "passive"))
      (node (ref "C37") (pin "1") (pinfunction "+_1") (pintype "passive"))
      (node (ref "C9") (pin "1") (pinfunction "1_1") (pintype "passive"))
      (node (ref "D6") (pin "A") (pinfunction "A_A") (pintype "passive"))
      (node (ref "J2") (pin "12V") (pinfunction "P$1_12V") (pintype "bidirectional"))
      (node (ref "Q2") (pin "TAB") (pinfunction "D_TAB") (pintype "bidirectional"))
      (node (ref "Q3") (pin "TAB") (pinfunction "D_TAB") (pintype "bidirectional"))
      (node (ref "Q5") (pin "TAB") (pinfunction "D_TAB") (pintype "bidirectional"))
      (node (ref "R26") (pin "1") (pinfunction "1_1") (pintype "passive"))
      (node (ref "U$1") (pin "29") (pinfunction "PVDD1_29") (pintype "bidirectional"))
      (node (ref "U$1") (pin "53") (pinfunction "PVDD2_53") (pintype "bidirectional"))
      (node (ref "U$1") (pin "54") (pinfunction "PVDD2_54") (pintype "bidirectional"))
      (node (ref "U$3") (pin "P$1") (pinfunction "P$1_P$1") (pintype "bidirectional"))
    )
    (net (code "71") (name "PVDDSENSE") (class "Default")
      (node (ref "C31") (pin "1") (pinfunction "1_1") (pintype "passive"))
      (node (ref "R26") (pin "2") (pinfunction "2_2") (pintype "passive"))
      (node (ref "R27") (pin "1") (pinfunction "1_1") (pintype "passive"))
      (node (ref "U$2") (pin "PD0") (pinfunction "PD0_PD0") (pintype "bidirectional"))
      (node (ref "U1") (pin "3") (pinfunction "I/O_2_3") (pintype "bidirectional"))
    )
    (net (code "72") (name "PWM_IN") (class "Default")
      (node (ref "J1") (pin "3") (pinfunction "3_3") (pintype "bidirectional"))
      (node (ref "U$2") (pin "PF4") (pinfunction "PF4_PF4") (pintype "bidirectional"))
    )
    (net (code "73") (name "PWRGD") (class "Default")
      (node (ref "R5") (pin "1") (pinfunction "1_1") (pintype "passive"))
      (node (ref "U$1") (pin "4") (pinfunction "PWRGD_4") (pintype "bidirectional"))
    )
    (net (code "74") (name "SCLK") (class "Default")
      (node (ref "U$1") (pin "11") (pinfunction "SCLK_11") (pintype "bidirectional"))
      (node (ref "U$2") (pin "PB4") (pinfunction "PB4_PB4") (pintype "bidirectional"))
    )
    (net (code "75") (name "SDI") (class "Default")
      (node (ref "U$1") (pin "9") (pinfunction "SDI_9") (pintype "bidirectional"))
      (node (ref "U$2") (pin "PB7") (pinfunction "PB7_PB7") (pintype "bidirectional"))
    )
    (net (code "76") (name "SDO") (class "Default")
      (node (ref "U$1") (pin "10") (pinfunction "SDO_10") (pintype "bidirectional"))
      (node (ref "U$2") (pin "PB6") (pinfunction "PB6_PB6") (pintype "bidirectional"))
    )
    (net (code "77") (name "SH_A") (class "Default")
      (node (ref "C13") (pin "2") (pinfunction "2_2") (pintype "passive"))
      (node (ref "D13") (pin "A") (pinfunction "A_A") (pintype "passive"))
      (node (ref "Q1") (pin "TAB") (pinfunction "D_TAB") (pintype "bidirectional"))
      (node (ref "Q2") (pin "2") (pinfunction "S_2") (pintype "bidirectional"))
      (node (ref "R14") (pin "1") (pinfunction "1_1") (pintype "passive"))
      (node (ref "U$1") (pin "46") (pinfunction "SH_A_46") (pintype "bidirectional"))
      (node (ref "U$25") (pin "P$1") (pinfunction "P$1_P$1") (pintype "bidirectional"))
      (node (ref "U$5") (pin "P$1") (pinfunction "P$1_P$1") (pintype "bidirectional"))
    )
    (net (code "78") (name "SH_B") (class "Default")
      (node (ref "C12") (pin "2") (pinfunction "2_2") (pintype "passive"))
      (node (ref "D11") (pin "A") (pinfunction "A_A") (pintype "passive"))
      (node (ref "Q3") (pin "2") (pinfunction "S_2") (pintype "bidirectional"))
      (node (ref "Q4") (pin "TAB") (pinfunction "D_TAB") (pintype "bidirectional"))
      (node (ref "R19") (pin "1") (pinfunction "1_1") (pintype "passive"))
      (node (ref "U$1") (pin "41") (pinfunction "SH_B_41") (pintype "bidirectional"))
      (node (ref "U$24") (pin "P$1") (pinfunction "P$1_P$1") (pintype "bidirectional"))
      (node (ref "U$6") (pin "P$1") (pinfunction "P$1_P$1") (pintype "bidirectional"))
    )
    (net (code "79") (name "SH_C") (class "Default")
      (node (ref "C11") (pin "2") (pinfunction "2_2") (pintype "passive"))
      (node (ref "D14") (pin "A") (pinfunction "A_A") (pintype "passive"))
      (node (ref "Q5") (pin "2") (pinfunction "S_2") (pintype "bidirectional"))
      (node (ref "Q6") (pin "TAB") (pinfunction "D_TAB") (pintype "bidirectional"))
      (node (ref "R24") (pin "1") (pinfunction "1_1") (pintype "passive"))
      (node (ref "U$1") (pin "36") (pinfunction "SH_C_36") (pintype "bidirectional"))
      (node (ref "U$20") (pin "P$1") (pinfunction "P$1_P$1") (pintype "bidirectional"))
      (node (ref "U$7") (pin "P$1") (pinfunction "P$1_P$1") (pintype "bidirectional"))
    )
    (net (code "80") (name "SL_A") (class "Default")
      (node (ref "C21") (pin "1") (pinfunction "1_1") (pintype "passive"))
      (node (ref "D12") (pin "A") (pinfunction "A_A") (pintype "passive"))
      (node (ref "Q1") (pin "2") (pinfunction "S_2") (pintype "bidirectional"))
      (node (ref "R13") (pin "2") (pinfunction "2_2") (pintype "passive"))
      (node (ref "U$1") (pin "33") (pinfunction "SN1_33") (pintype "bidirectional"))
      (node (ref "U$1") (pin "44") (pinfunction "SL_A_44") (pintype "bidirectional"))
    )
    (net (code "81") (name "SL_B") (class "Default")
      (node (ref "C24") (pin "1") (pinfunction "1_1") (pintype "passive"))
      (node (ref "D10") (pin "A") (pinfunction "A_A") (pintype "passive"))
      (node (ref "Q4") (pin "2") (pinfunction "S_2") (pintype "bidirectional"))
      (node (ref "R18") (pin "2") (pinfunction "2_2") (pintype "passive"))
      (node (ref "U$1") (pin "31") (pinfunction "SN2_31") (pintype "bidirectional"))
      (node (ref "U$1") (pin "39") (pinfunction "SL_B_39") (pintype "bidirectional"))
    )
    (net (code "82") (name "SO1") (class "Default")
      (node (ref "C6") (pin "1") (pinfunction "1_1") (pintype "passive"))
      (node (ref "R9") (pin "2") (pinfunction "2_2") (pintype "passive"))
      (node (ref "U$2") (pin "PE1") (pinfunction "PE1_PE1") (pintype "bidirectional"))
    )
    (net (code "83") (name "SO2") (class "Default")
      (node (ref "C7") (pin "1") (pinfunction "1_1") (pintype "passive"))
      (node (ref "R10") (pin "2") (pinfunction "2_2") (pintype "passive"))
      (node (ref "U$2") (pin "PE2") (pinfunction "PE2_PE2") (pintype "bidirectional"))
    )
    (net (code "84") (name "UART_RX") (class "Default")
      (node (ref "U$2") (pin "PB0") (pinfunction "PB0_PB0") (pintype "bidirectional"))
      (node (ref "U2") (pin "12") (pinfunction "R1OUT_12") (pintype "bidirectional"))
    )
    (net (code "85") (name "UART_TX") (class "Default")
      (node (ref "U$2") (pin "PB1") (pinfunction "PB1_PB1") (pintype "bidirectional"))
      (node (ref "U2") (pin "11") (pinfunction "T1IN_11") (pintype "bidirectional"))
    )
    (net (code "86") (name "VCC") (class "Default")
      (node (ref "C32") (pin "2") (pinfunction "2_2") (pintype "passive"))
      (node (ref "C33") (pin "2") (pinfunction "2_2") (pintype "passive"))
      (node (ref "C36") (pin "1") (pinfunction "+_1") (pintype "passive"))
      (node (ref "C46") (pin "1") (pinfunction "1_1") (pintype "passive"))
      (node (ref "D7") (pin "A") (pinfunction "A_A") (pintype "passive"))
      (node (ref "Q7") (pin "2") (pinfunction "S_2") (pintype "passive"))
      (node (ref "Q8") (pin "2") (pinfunction "S_2") (pintype "passive"))
      (node (ref "R3") (pin "2") (pinfunction "2_2") (pintype "passive"))
      (node (ref "R5") (pin "2") (pinfunction "2_2") (pintype "passive"))
      (node (ref "R6") (pin "2") (pinfunction "2_2") (pintype "passive"))
      (node (ref "R7") (pin "2") (pinfunction "2_2") (pintype "passive"))
      (node (ref "U$1") (pin "24") (pinfunction "REF_24") (pintype "bidirectional"))
      (node (ref "U$1") (pin "49") (pinfunction "VDD_SPI_49") (pintype "bidirectional"))
      (node (ref "U$10") (pin "P$1") (pinfunction "P$1_P$1") (pintype "bidirectional"))
      (node (ref "U$14") (pin "P$2") (pinfunction "P$2_P$2") (pintype "bidirectional"))
      (node (ref "U$2") (pin "+3V3") (pinfunction "+3V3_+3V3") (pintype "power_in"))
      (node (ref "U1") (pin "5") (pinfunction "VP_5") (pintype "bidirectional"))
      (node (ref "U2") (pin "16") (pinfunction "VCC_16") (pintype "bidirectional"))
    )
    (net (code "87") (name "unconnected-(J1-Pad2)") (class "Default")
      (node (ref "J1") (pin "2") (pinfunction "2_2") (pintype "bidirectional"))
    )
    (net (code "88") (name "unconnected-(U$1-EN_BUCK-Pad55)") (class "Default")
      (node (ref "U$1") (pin "55") (pinfunction "EN_BUCK_55") (pintype "bidirectional"))
    )
    (net (code "89") (name "unconnected-(U$2-PadPA2)") (class "Default")
      (node (ref "U$2") (pin "PA2") (pinfunction "PA2_PA2") (pintype "bidirectional"))
    )
    (net (code "90") (name "unconnected-(U$2-PadPD7)") (class "Default")
      (node (ref "U$2") (pin "PD7") (pinfunction "PD7_PD7") (pintype "bidirectional"))
    )
    (net (code "91") (name "unconnected-(U$2-PadPE0)") (class "Default")
      (node (ref "U$2") (pin "PE0") (pinfunction "PE0_PE0") (pintype "bidirectional"))
    )
    (net (code "92") (name "unconnected-(U$2-PadPE3)") (class "Default")
      (node (ref "U$2") (pin "PE3") (pinfunction "PE3_PE3") (pintype "bidirectional"))
    )
    (net (code "93") (name "unconnected-(U$2-PadPE4)") (class "Default")
      (node (ref "U$2") (pin "PE4") (pinfunction "PE4_PE4") (pintype "bidirectional"))
    )
    (net (code "94") (name "unconnected-(U$2-PadPF0)") (class "Default")
      (node (ref "U$2") (pin "PF0") (pinfunction "PF0_PF0") (pintype "bidirectional"))
    )
    (net (code "95") (name "unconnected-(U$2-PadPF1)") (class "Default")
      (node (ref "U$2") (pin "PF1") (pinfunction "PF1_PF1") (pintype "bidirectional"))
    )
    (net (code "96") (name "unconnected-(U$4-Pad1)") (class "Default")
      (node (ref "U$4") (pin "1") (pinfunction "1_1") (pintype "bidirectional"))
    )
    (net (code "97") (name "unconnected-(U$4-Pad2)") (class "Default")
      (node (ref "U$4") (pin "2") (pinfunction "2_2") (pintype "bidirectional"))
    )
    (net (code "98") (name "unconnected-(U2-R2IN-Pad8)") (class "Default")
      (node (ref "U2") (pin "8") (pinfunction "R2IN_8") (pintype "bidirectional"))
    )
    (net (code "99") (name "unconnected-(U2-R2OUT-Pad9)") (class "Default")
      (node (ref "U2") (pin "9") (pinfunction "R2OUT_9") (pintype "bidirectional"))
    )
    (net (code "100") (name "unconnected-(U2-T2IN-Pad10)") (class "Default")
      (node (ref "U2") (pin "10") (pinfunction "T2IN_10") (pintype "bidirectional"))
    )
    (net (code "101") (name "unconnected-(U2-T2OUT-Pad7)") (class "Default")
      (node (ref "U2") (pin "7") (pinfunction "T2OUT_7") (pintype "bidirectional"))
    )
  )
)
